# Spindle_Drive.net
KiCad netlist of a schematic drawn in Altium Designer
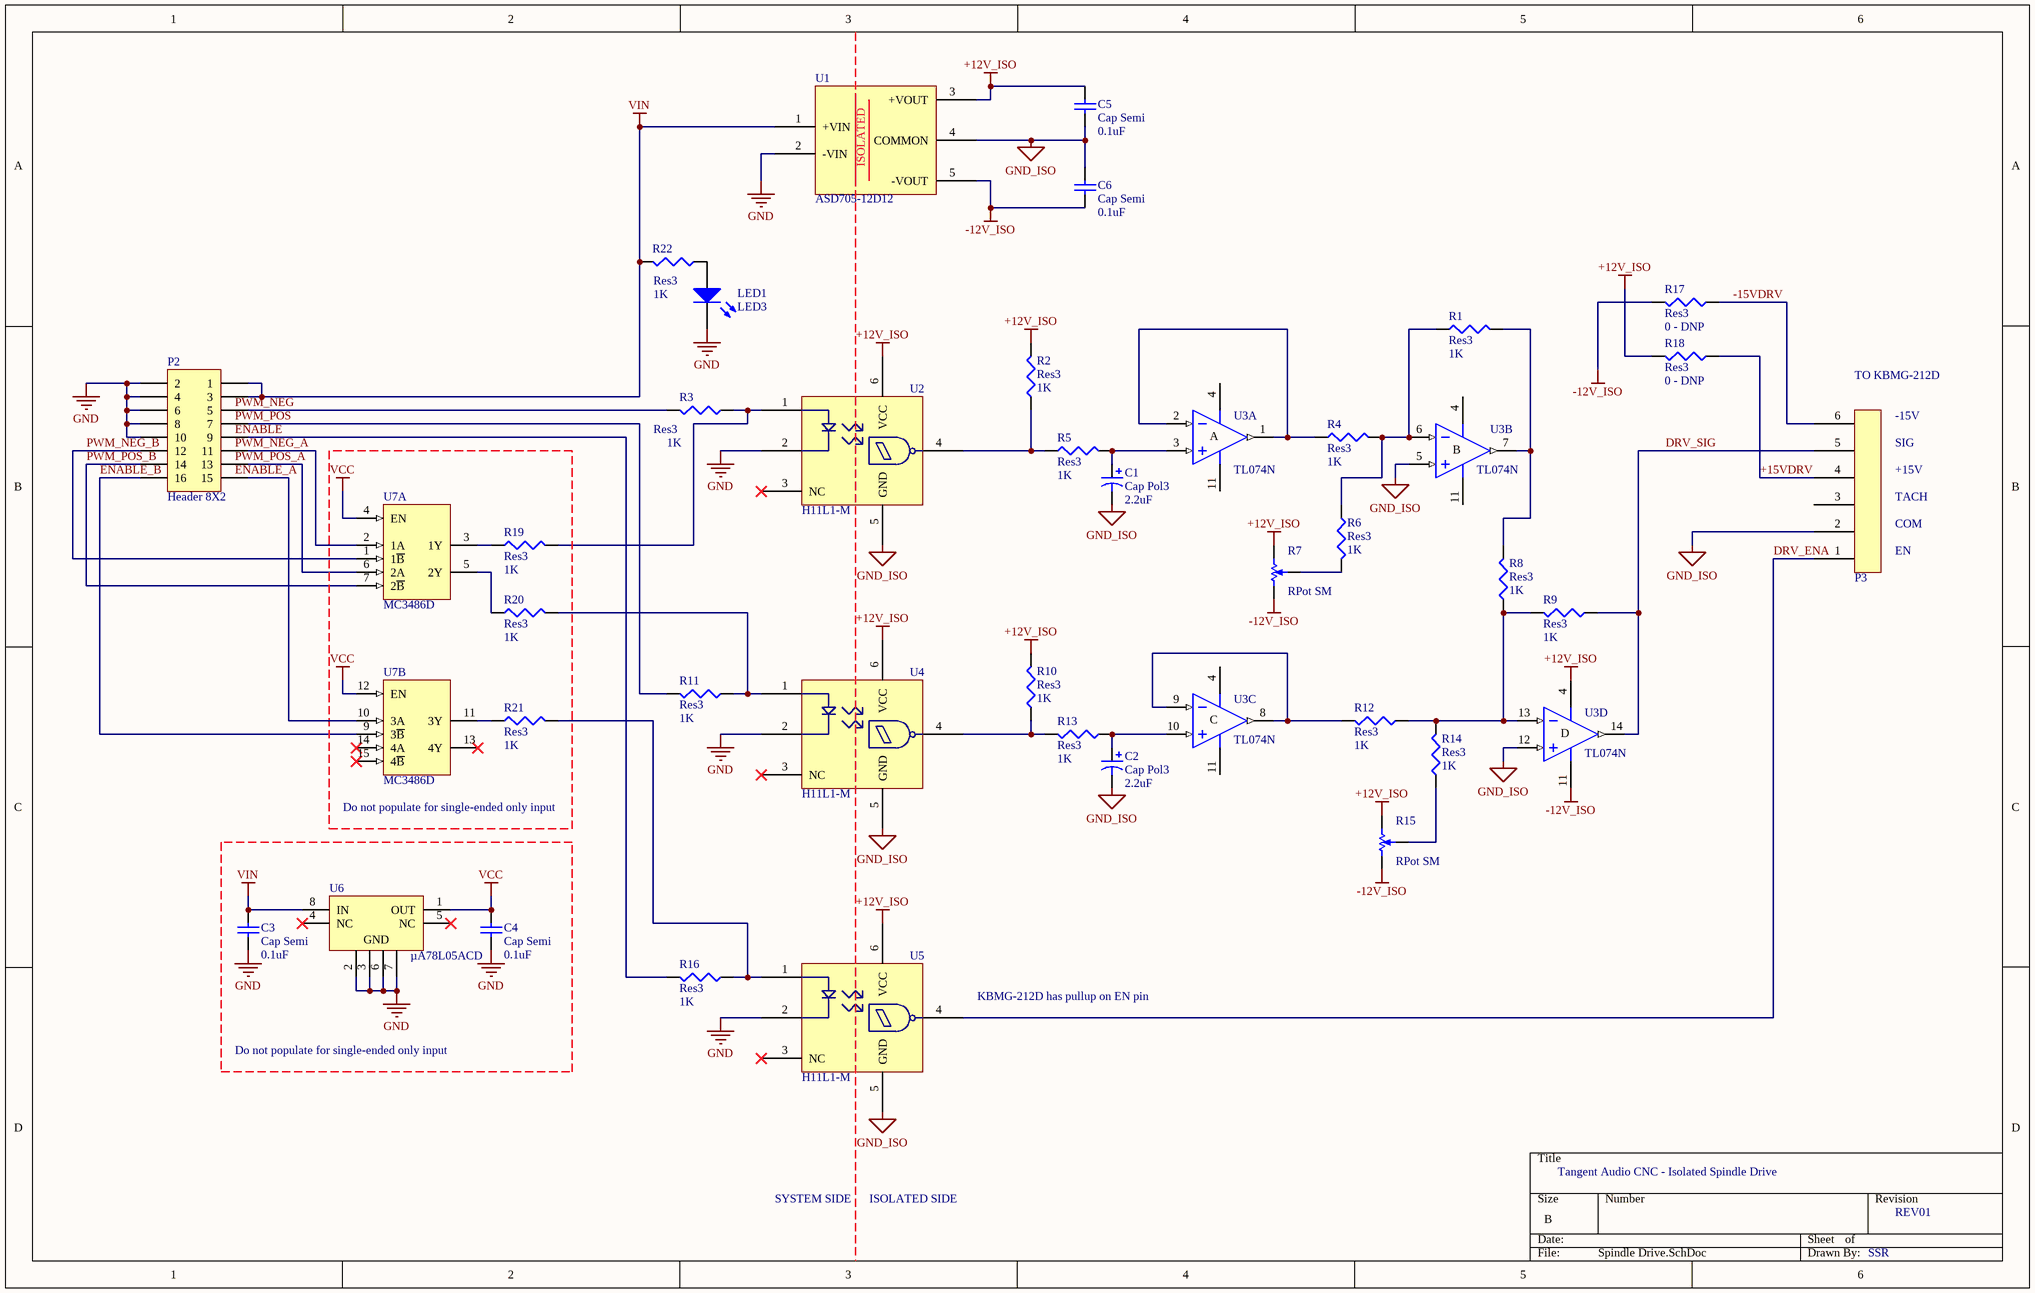
[diagram p0: Spindle Drive.SchDoc]

(export (version "E")
  (design (tool "Eeschema 10.0.6"))
  (components
    (comp (ref "C1")
      (value "Cap Pol3")
      (description "Polarized Capacitor (Surface Mount)")
      (fields (field (name "ALTIUM_VALUE") "2.2uF") (field (name "PUBLISHER") "Altium Limited"))
      (libsource (lib "Miscellaneous Devices") (part "Cap Pol3"))
    )
    (comp (ref "C2")
      (value "Cap Pol3")
      (description "Polarized Capacitor (Surface Mount)")
      (fields (field (name "ALTIUM_VALUE") "2.2uF") (field (name "PUBLISHER") "Altium Limited"))
      (libsource (lib "Miscellaneous Devices") (part "Cap Pol3"))
    )
    (comp (ref "C3")
      (value "Cap Semi")
      (footprint "1608[0603]")
      (description "Capacitor (Semiconductor SIM Model)")
      (fields (field (name "ALTIUM_VALUE") "0.1uF") (field (name "PUBLISHER") "Altium Limited"))
      (libsource (lib "Miscellaneous Devices") (part "Cap Semi"))
    )
    (comp (ref "C4")
      (value "Cap Semi")
      (footprint "1608[0603]")
      (description "Capacitor (Semiconductor SIM Model)")
      (fields (field (name "ALTIUM_VALUE") "0.1uF") (field (name "PUBLISHER") "Altium Limited"))
      (libsource (lib "Miscellaneous Devices") (part "Cap Semi"))
    )
    (comp (ref "C5")
      (value "Cap Semi")
      (footprint "1608[0603]")
      (description "Capacitor (Semiconductor SIM Model)")
      (fields (field (name "ALTIUM_VALUE") "0.1uF") (field (name "PUBLISHER") "Altium Limited"))
      (libsource (lib "Miscellaneous Devices") (part "Cap Semi"))
    )
    (comp (ref "C6")
      (value "Cap Semi")
      (footprint "1608[0603]")
      (description "Capacitor (Semiconductor SIM Model)")
      (fields (field (name "ALTIUM_VALUE") "0.1uF") (field (name "PUBLISHER") "Altium Limited"))
      (libsource (lib "Miscellaneous Devices") (part "Cap Semi"))
    )
    (comp (ref "LED1")
      (value "LED3")
      (footprint "3.5X2.8X1.9")
      (description "Typical BLUE SiC LED")
      (fields (field (name "PUBLISHER") "Altium Limited"))
      (libsource (lib "Miscellaneous Devices") (part "LED3"))
    )
    (comp (ref "P2")
      (value "Header 8X2")
      (footprint "IDC2.54-V16D")
      (description "Header, 8-Pin, Dual row")
      (fields (field (name "PUBLISHER") "Altium Limited"))
      (libsource (lib "Miscellaneous Connectors") (part "Header 8X2"))
    )
    (comp (ref "P3")
      (value "Phoenix_1933228")
      (footprint "Phoenix_1933228")
      (libsource (lib "GechoBreakout") (part "Phoenix_1933228"))
    )
    (comp (ref "R1")
      (value "Res3")
      (footprint "J1-0603")
      (description "Resistor")
      (fields (field (name "ALTIUM_VALUE") "1K") (field (name "PUBLISHER") "Altium Limited"))
      (libsource (lib "Miscellaneous Devices") (part "Res3"))
    )
    (comp (ref "R2")
      (value "Res3")
      (footprint "J1-0603")
      (description "Resistor")
      (fields (field (name "ALTIUM_VALUE") "1K") (field (name "PUBLISHER") "Altium Limited"))
      (libsource (lib "Miscellaneous Devices") (part "Res3"))
    )
    (comp (ref "R3")
      (value "Res3")
      (footprint "J1-0603")
      (description "Resistor")
      (fields (field (name "ALTIUM_VALUE") "1K") (field (name "PUBLISHER") "Altium Limited"))
      (libsource (lib "Miscellaneous Devices") (part "Res3"))
    )
    (comp (ref "R4")
      (value "Res3")
      (footprint "J1-0603")
      (description "Resistor")
      (fields (field (name "ALTIUM_VALUE") "1K") (field (name "PUBLISHER") "Altium Limited"))
      (libsource (lib "Miscellaneous Devices") (part "Res3"))
    )
    (comp (ref "R5")
      (value "Res3")
      (footprint "J1-0603")
      (description "Resistor")
      (fields (field (name "ALTIUM_VALUE") "1K") (field (name "PUBLISHER") "Altium Limited"))
      (libsource (lib "Miscellaneous Devices") (part "Res3"))
    )
    (comp (ref "R6")
      (value "Res3")
      (footprint "J1-0603")
      (description "Resistor")
      (fields (field (name "ALTIUM_VALUE") "1K") (field (name "PUBLISHER") "Altium Limited"))
      (libsource (lib "Miscellaneous Devices") (part "Res3"))
    )
    (comp (ref "R7")
      (value "RPot SM")
      (footprint "Copal_ST-4EA")
      (description "Square Trimming Potentiometer")
      (fields (field (name "PUBLISHER") "Altium Limited"))
      (libsource (lib "Miscellaneous Devices") (part "RPot SM"))
    )
    (comp (ref "R8")
      (value "Res3")
      (footprint "J1-0603")
      (description "Resistor")
      (fields (field (name "ALTIUM_VALUE") "1K") (field (name "PUBLISHER") "Altium Limited"))
      (libsource (lib "Miscellaneous Devices") (part "Res3"))
    )
    (comp (ref "R9")
      (value "Res3")
      (footprint "J1-0603")
      (description "Resistor")
      (fields (field (name "ALTIUM_VALUE") "1K") (field (name "PUBLISHER") "Altium Limited"))
      (libsource (lib "Miscellaneous Devices") (part "Res3"))
    )
    (comp (ref "R10")
      (value "Res3")
      (footprint "J1-0603")
      (description "Resistor")
      (fields (field (name "ALTIUM_VALUE") "1K") (field (name "PUBLISHER") "Altium Limited"))
      (libsource (lib "Miscellaneous Devices") (part "Res3"))
    )
    (comp (ref "R11")
      (value "Res3")
      (footprint "J1-0603")
      (description "Resistor")
      (fields (field (name "ALTIUM_VALUE") "1K") (field (name "PUBLISHER") "Altium Limited"))
      (libsource (lib "Miscellaneous Devices") (part "Res3"))
    )
    (comp (ref "R12")
      (value "Res3")
      (footprint "J1-0603")
      (description "Resistor")
      (fields (field (name "ALTIUM_VALUE") "1K") (field (name "PUBLISHER") "Altium Limited"))
      (libsource (lib "Miscellaneous Devices") (part "Res3"))
    )
    (comp (ref "R13")
      (value "Res3")
      (footprint "J1-0603")
      (description "Resistor")
      (fields (field (name "ALTIUM_VALUE") "1K") (field (name "PUBLISHER") "Altium Limited"))
      (libsource (lib "Miscellaneous Devices") (part "Res3"))
    )
    (comp (ref "R14")
      (value "Res3")
      (footprint "J1-0603")
      (description "Resistor")
      (fields (field (name "ALTIUM_VALUE") "1K") (field (name "PUBLISHER") "Altium Limited"))
      (libsource (lib "Miscellaneous Devices") (part "Res3"))
    )
    (comp (ref "R15")
      (value "RPot SM")
      (footprint "Copal_ST-4EA")
      (description "Square Trimming Potentiometer")
      (fields (field (name "PUBLISHER") "Altium Limited"))
      (libsource (lib "Miscellaneous Devices") (part "RPot SM"))
    )
    (comp (ref "R16")
      (value "Res3")
      (footprint "J1-0603")
      (description "Resistor")
      (fields (field (name "ALTIUM_VALUE") "1K") (field (name "PUBLISHER") "Altium Limited"))
      (libsource (lib "Miscellaneous Devices") (part "Res3"))
    )
    (comp (ref "R17")
      (value "Res3")
      (footprint "J1-0603")
      (description "Resistor")
      (fields (field (name "ALTIUM_VALUE") "0 - DNP") (field (name "PUBLISHER") "Altium Limited"))
      (libsource (lib "Miscellaneous Devices") (part "Res3"))
    )
    (comp (ref "R18")
      (value "Res3")
      (footprint "J1-0603")
      (description "Resistor")
      (fields (field (name "ALTIUM_VALUE") "0 - DNP") (field (name "PUBLISHER") "Altium Limited"))
      (libsource (lib "Miscellaneous Devices") (part "Res3"))
    )
    (comp (ref "R19")
      (value "Res3")
      (footprint "J1-0603")
      (description "Resistor")
      (fields (field (name "ALTIUM_VALUE") "1K") (field (name "PUBLISHER") "Altium Limited"))
      (libsource (lib "Miscellaneous Devices") (part "Res3"))
    )
    (comp (ref "R20")
      (value "Res3")
      (footprint "J1-0603")
      (description "Resistor")
      (fields (field (name "ALTIUM_VALUE") "1K") (field (name "PUBLISHER") "Altium Limited"))
      (libsource (lib "Miscellaneous Devices") (part "Res3"))
    )
    (comp (ref "R21")
      (value "Res3")
      (footprint "J1-0603")
      (description "Resistor")
      (fields (field (name "ALTIUM_VALUE") "1K") (field (name "PUBLISHER") "Altium Limited"))
      (libsource (lib "Miscellaneous Devices") (part "Res3"))
    )
    (comp (ref "R22")
      (value "Res3")
      (footprint "J1-0603")
      (description "Resistor")
      (fields (field (name "ALTIUM_VALUE") "1K") (field (name "PUBLISHER") "Altium Limited"))
      (libsource (lib "Miscellaneous Devices") (part "Res3"))
    )
    (comp (ref "U1")
      (value "ASD705-12D12")
      (footprint "Astrodyne_ASD705")
      (description "Astrodyne 9-18VDC in, +/-12VDC out iso regulated DC-DC")
      (libsource (lib "Spindle Drive") (part "ASD705-12D12"))
    )
    (comp (ref "U2")
      (value "H11L1-M")
      (footprint "H11L3M_SMT")
      (libsource (lib "Spindle Drive") (part "H11L1-M"))
    )
    (comp (ref "U3")
      (value "TL074N")
      (footprint "SOIC127P600-14AN")
      (description "Low-Noise JFET-Input Operational Amplifier")
      (fields (field (name "PUBLISHER") "Altium Limited"))
      (libsource (lib "TI Operational Amplifier") (part "TL074N"))
    )
    (comp (ref "U4")
      (value "H11L1-M")
      (footprint "H11L3M_SMT")
      (libsource (lib "Spindle Drive") (part "H11L1-M"))
    )
    (comp (ref "U5")
      (value "H11L1-M")
      (footprint "H11L3M_SMT")
      (libsource (lib "Spindle Drive") (part "H11L1-M"))
    )
    (comp (ref "U6")
      (value "µA78L05ACD")
      (footprint "D008_L")
      (description "Positive-Voltage Regulator")
      (fields (field (name "PUBLISHER") "Altium Limited"))
      (libsource (lib "TI Power Mgt Voltage Regulator") (part "µA78L05ACD"))
    )
    (comp (ref "U7")
      (value "MC3486D")
      (footprint "D016_N")
      (description "Quadruple Line Receiver with 3-State Output")
      (fields (field (name "PUBLISHER") "Altium Limited"))
      (libsource (lib "TI Interface Line Receiver") (part "MC3486D"))
    )
  )
  (nets
    (net (code "1") (name "+12V_ISO") (class "Default")
      (node (ref "C5") (pin "1") (pinfunction "1_1") (pintype "passive"))
      (node (ref "R10") (pin "2") (pinfunction "2_2") (pintype "passive"))
      (node (ref "R15") (pin "CW") (pinfunction "+_CW") (pintype "passive"))
      (node (ref "R18") (pin "2") (pinfunction "2_2") (pintype "passive"))
      (node (ref "R2") (pin "2") (pinfunction "2_2") (pintype "passive"))
      (node (ref "R7") (pin "CW") (pinfunction "+_CW") (pintype "passive"))
      (node (ref "U1") (pin "3") (pinfunction "+VOUT_3") (pintype "power_in"))
      (node (ref "U2") (pin "6") (pinfunction "VCC_6") (pintype "power_in"))
      (node (ref "U3") (pin "4") (pinfunction "V+_4") (pintype "power_in"))
      (node (ref "U4") (pin "6") (pinfunction "VCC_6") (pintype "power_in"))
      (node (ref "U5") (pin "6") (pinfunction "VCC_6") (pintype "power_in"))
    )
    (net (code "2") (name "-12V_ISO") (class "Default")
      (node (ref "C6") (pin "1") (pinfunction "1_1") (pintype "passive"))
      (node (ref "R15") (pin "CCW") (pinfunction "-_CCW") (pintype "passive"))
      (node (ref "R17") (pin "2") (pinfunction "2_2") (pintype "passive"))
      (node (ref "R7") (pin "CCW") (pinfunction "-_CCW") (pintype "passive"))
      (node (ref "U1") (pin "5") (pinfunction "-VOUT_5") (pintype "power_in"))
      (node (ref "U3") (pin "11") (pinfunction "V-_11") (pintype "power_in"))
    )
    (net (code "3") (name "/+15VDRV") (class "Default")
      (node (ref "P3") (pin "4") (pinfunction "4_4") (pintype "passive"))
      (node (ref "R18") (pin "1") (pinfunction "1_1") (pintype "passive"))
    )
    (net (code "4") (name "/-15VDRV") (class "Default")
      (node (ref "P3") (pin "6") (pinfunction "6_6") (pintype "passive"))
      (node (ref "R17") (pin "1") (pinfunction "1_1") (pintype "passive"))
    )
    (net (code "5") (name "/DRV_ENA") (class "Default")
      (node (ref "P3") (pin "1") (pinfunction "1_1") (pintype "passive"))
      (node (ref "U5") (pin "4") (pinfunction "VO_4") (pintype "passive"))
    )
    (net (code "6") (name "/DRV_SIG") (class "Default")
      (node (ref "P3") (pin "5") (pinfunction "5_5") (pintype "passive"))
      (node (ref "R9") (pin "1") (pinfunction "1_1") (pintype "passive"))
      (node (ref "U3") (pin "14") (pinfunction "OUT_14") (pintype "output"))
    )
    (net (code "9") (name "/ENABLE_B") (class "Default")
      (node (ref "P2") (pin "16") (pinfunction "16_16") (pintype "passive"))
      (node (ref "U7") (pin "9") (pinfunction "3~{B}_9") (pintype "input"))
    )
    (net (code "12") (name "/PWM_NEG_B") (class "Default")
      (node (ref "P2") (pin "12") (pinfunction "12_12") (pintype "passive"))
      (node (ref "U7") (pin "1") (pinfunction "1~{B}_1") (pintype "input"))
    )
    (net (code "15") (name "/PWM_POS_B") (class "Default")
      (node (ref "P2") (pin "14") (pinfunction "14_14") (pintype "passive"))
      (node (ref "U7") (pin "7") (pinfunction "2~{B}_7") (pintype "input"))
    )
    (net (code "16") (name "GND") (class "Default")
      (node (ref "C3") (pin "1") (pinfunction "1_1") (pintype "passive"))
      (node (ref "C4") (pin "1") (pinfunction "1_1") (pintype "passive"))
      (node (ref "LED1") (pin "2") (pinfunction "K_2") (pintype "passive"))
      (node (ref "P2") (pin "10") (pinfunction "10_10") (pintype "passive"))
      (node (ref "P2") (pin "2") (pinfunction "2_2") (pintype "passive"))
      (node (ref "P2") (pin "4") (pinfunction "4_4") (pintype "passive"))
      (node (ref "P2") (pin "6") (pinfunction "6_6") (pintype "passive"))
      (node (ref "P2") (pin "8") (pinfunction "8_8") (pintype "passive"))
      (node (ref "U1") (pin "2") (pinfunction "-VIN_2") (pintype "power_in"))
      (node (ref "U2") (pin "2") (pinfunction "K_2") (pintype "passive"))
      (node (ref "U4") (pin "2") (pinfunction "K_2") (pintype "passive"))
      (node (ref "U5") (pin "2") (pinfunction "K_2") (pintype "passive"))
      (node (ref "U6") (pin "2") (pinfunction "GND_2") (pintype "power_in"))
      (node (ref "U6") (pin "3") (pinfunction "GND_3") (pintype "power_in"))
      (node (ref "U6") (pin "6") (pinfunction "GND_6") (pintype "power_in"))
      (node (ref "U6") (pin "7") (pinfunction "GND_7") (pintype "power_in"))
      (node (ref "U7") (pin "8") (pinfunction "GND_8") (pintype "power_in"))
    )
    (net (code "17") (name "GND_ISO") (class "Default")
      (node (ref "C1") (pin "2") (pinfunction "2_2") (pintype "passive"))
      (node (ref "C2") (pin "2") (pinfunction "2_2") (pintype "passive"))
      (node (ref "C5") (pin "2") (pinfunction "2_2") (pintype "passive"))
      (node (ref "C6") (pin "2") (pinfunction "2_2") (pintype "passive"))
      (node (ref "P3") (pin "2") (pinfunction "2_2") (pintype "passive"))
      (node (ref "U1") (pin "4") (pinfunction "COMMON_4") (pintype "power_in"))
      (node (ref "U2") (pin "5") (pinfunction "GND_5") (pintype "power_in"))
      (node (ref "U3") (pin "12") (pinfunction "IN+_12") (pintype "input"))
      (node (ref "U3") (pin "5") (pinfunction "IN+_5") (pintype "input"))
      (node (ref "U4") (pin "5") (pinfunction "GND_5") (pintype "power_in"))
      (node (ref "U5") (pin "5") (pinfunction "GND_5") (pintype "power_in"))
    )
    (net (code "18") (name "Net-(LED1-A)") (class "Default")
      (node (ref "LED1") (pin "1") (pinfunction "A_1") (pintype "passive"))
      (node (ref "R22") (pin "1") (pinfunction "1_1") (pintype "passive"))
    )
    (net (code "19") (name "Net-(P2-Pad5)") (class "Default")
      (node (ref "P2") (pin "5") (pinfunction "5_5") (pintype "passive"))
      (node (ref "R3") (pin "2") (pinfunction "2_2") (pintype "passive"))
    )
    (net (code "20") (name "Net-(P2-Pad7)") (class "Default")
      (node (ref "P2") (pin "7") (pinfunction "7_7") (pintype "passive"))
      (node (ref "R11") (pin "2") (pinfunction "2_2") (pintype "passive"))
    )
    (net (code "21") (name "Net-(P2-Pad9)") (class "Default")
      (node (ref "P2") (pin "9") (pinfunction "9_9") (pintype "passive"))
      (node (ref "R16") (pin "2") (pinfunction "2_2") (pintype "passive"))
    )
    (net (code "22") (name "Net-(R6-Pad2)") (class "Default")
      (node (ref "R6") (pin "2") (pinfunction "2_2") (pintype "passive"))
      (node (ref "R7") (pin "W") (pinfunction "W_W") (pintype "passive"))
    )
    (net (code "23") (name "Net-(R14-Pad1)") (class "Default")
      (node (ref "R14") (pin "1") (pinfunction "1_1") (pintype "passive"))
      (node (ref "R15") (pin "W") (pinfunction "W_W") (pintype "passive"))
    )
    (net (code "24") (name "Net-(U2-A)") (class "Default")
      (node (ref "R19") (pin "2") (pinfunction "2_2") (pintype "passive"))
      (node (ref "R3") (pin "1") (pinfunction "1_1") (pintype "passive"))
      (node (ref "U2") (pin "1") (pinfunction "A_1") (pintype "passive"))
    )
    (net (code "25") (name "Net-(U2-VO)") (class "Default")
      (node (ref "R2") (pin "1") (pinfunction "1_1") (pintype "passive"))
      (node (ref "R5") (pin "1") (pinfunction "1_1") (pintype "passive"))
      (node (ref "U2") (pin "4") (pinfunction "VO_4") (pintype "passive"))
    )
    (net (code "26") (name "Net-(U3A-IN+)") (class "Default")
      (node (ref "C1") (pin "1") (pinfunction "1_1") (pintype "passive"))
      (node (ref "R5") (pin "2") (pinfunction "2_2") (pintype "passive"))
      (node (ref "U3") (pin "3") (pinfunction "IN+_3") (pintype "input"))
    )
    (net (code "27") (name "Net-(U3A-IN-)") (class "Default")
      (node (ref "R4") (pin "1") (pinfunction "1_1") (pintype "passive"))
      (node (ref "U3") (pin "1") (pinfunction "OUT_1") (pintype "output"))
      (node (ref "U3") (pin "2") (pinfunction "IN-_2") (pintype "input"))
    )
    (net (code "28") (name "Net-(U3B-IN-)") (class "Default")
      (node (ref "R1") (pin "1") (pinfunction "1_1") (pintype "passive"))
      (node (ref "R4") (pin "2") (pinfunction "2_2") (pintype "passive"))
      (node (ref "R6") (pin "1") (pinfunction "1_1") (pintype "passive"))
      (node (ref "U3") (pin "6") (pinfunction "IN-_6") (pintype "input"))
    )
    (net (code "29") (name "Net-(U3B-OUT)") (class "Default")
      (node (ref "R1") (pin "2") (pinfunction "2_2") (pintype "passive"))
      (node (ref "R8") (pin "2") (pinfunction "2_2") (pintype "passive"))
      (node (ref "U3") (pin "7") (pinfunction "OUT_7") (pintype "output"))
    )
    (net (code "30") (name "Net-(U3C-IN+)") (class "Default")
      (node (ref "C2") (pin "1") (pinfunction "1_1") (pintype "passive"))
      (node (ref "R13") (pin "1") (pinfunction "1_1") (pintype "passive"))
      (node (ref "U3") (pin "10") (pinfunction "IN+_10") (pintype "input"))
    )
    (net (code "31") (name "Net-(U3C-IN-)") (class "Default")
      (node (ref "R12") (pin "2") (pinfunction "2_2") (pintype "passive"))
      (node (ref "U3") (pin "8") (pinfunction "OUT_8") (pintype "output"))
      (node (ref "U3") (pin "9") (pinfunction "IN-_9") (pintype "input"))
    )
    (net (code "32") (name "Net-(U3D-IN-)") (class "Default")
      (node (ref "R12") (pin "1") (pinfunction "1_1") (pintype "passive"))
      (node (ref "R14") (pin "2") (pinfunction "2_2") (pintype "passive"))
      (node (ref "R8") (pin "1") (pinfunction "1_1") (pintype "passive"))
      (node (ref "R9") (pin "2") (pinfunction "2_2") (pintype "passive"))
      (node (ref "U3") (pin "13") (pinfunction "IN-_13") (pintype "input"))
    )
    (net (code "33") (name "Net-(U4-A)") (class "Default")
      (node (ref "R11") (pin "1") (pinfunction "1_1") (pintype "passive"))
      (node (ref "R20") (pin "2") (pinfunction "2_2") (pintype "passive"))
      (node (ref "U4") (pin "1") (pinfunction "A_1") (pintype "passive"))
    )
    (net (code "34") (name "Net-(U4-VO)") (class "Default")
      (node (ref "R10") (pin "1") (pinfunction "1_1") (pintype "passive"))
      (node (ref "R13") (pin "2") (pinfunction "2_2") (pintype "passive"))
      (node (ref "U4") (pin "4") (pinfunction "VO_4") (pintype "passive"))
    )
    (net (code "35") (name "Net-(U5-A)") (class "Default")
      (node (ref "R16") (pin "1") (pinfunction "1_1") (pintype "passive"))
      (node (ref "R21") (pin "2") (pinfunction "2_2") (pintype "passive"))
      (node (ref "U5") (pin "1") (pinfunction "A_1") (pintype "passive"))
    )
    (net (code "36") (name "Net-(U7A-1A)") (class "Default")
      (node (ref "P2") (pin "11") (pinfunction "11_11") (pintype "passive"))
      (node (ref "U7") (pin "2") (pinfunction "1A_2") (pintype "input"))
    )
    (net (code "37") (name "Net-(U7A-1Y)") (class "Default")
      (node (ref "R19") (pin "1") (pinfunction "1_1") (pintype "passive"))
      (node (ref "U7") (pin "3") (pinfunction "1Y_3") (pintype "tri_state"))
    )
    (net (code "38") (name "Net-(U7A-2A)") (class "Default")
      (node (ref "P2") (pin "13") (pinfunction "13_13") (pintype "passive"))
      (node (ref "U7") (pin "6") (pinfunction "2A_6") (pintype "input"))
    )
    (net (code "39") (name "Net-(U7A-2Y)") (class "Default")
      (node (ref "R20") (pin "1") (pinfunction "1_1") (pintype "passive"))
      (node (ref "U7") (pin "5") (pinfunction "2Y_5") (pintype "tri_state"))
    )
    (net (code "40") (name "Net-(U7B-3A)") (class "Default")
      (node (ref "P2") (pin "15") (pinfunction "15_15") (pintype "passive"))
      (node (ref "U7") (pin "10") (pinfunction "3A_10") (pintype "input"))
    )
    (net (code "41") (name "Net-(U7B-3Y)") (class "Default")
      (node (ref "R21") (pin "1") (pinfunction "1_1") (pintype "passive"))
      (node (ref "U7") (pin "11") (pinfunction "3Y_11") (pintype "tri_state"))
    )
    (net (code "42") (name "VCC") (class "Default")
      (node (ref "C4") (pin "2") (pinfunction "2_2") (pintype "passive"))
      (node (ref "U6") (pin "1") (pinfunction "OUT_1") (pintype "power_in"))
      (node (ref "U7") (pin "12") (pinfunction "EN_12") (pintype "input"))
      (node (ref "U7") (pin "16") (pinfunction "VCC_16") (pintype "power_in"))
      (node (ref "U7") (pin "4") (pinfunction "EN_4") (pintype "input"))
    )
    (net (code "43") (name "VIN") (class "Default")
      (node (ref "C3") (pin "2") (pinfunction "2_2") (pintype "passive"))
      (node (ref "P2") (pin "1") (pinfunction "1_1") (pintype "passive"))
      (node (ref "P2") (pin "3") (pinfunction "3_3") (pintype "passive"))
      (node (ref "R22") (pin "2") (pinfunction "2_2") (pintype "passive"))
      (node (ref "U1") (pin "1") (pinfunction "+VIN_1") (pintype "power_in"))
      (node (ref "U6") (pin "8") (pinfunction "IN_8") (pintype "power_in"))
    )
    (net (code "44") (name "unconnected-(P3-Pad3)") (class "Default")
      (node (ref "P3") (pin "3") (pinfunction "3_3") (pintype "passive"))
    )
    (net (code "45") (name "unconnected-(U2-NC-Pad3)") (class "Default")
      (node (ref "U2") (pin "3") (pinfunction "NC_3") (pintype "passive+no_connect"))
    )
    (net (code "46") (name "unconnected-(U3A-V+-Pad4)") (class "Default")
      (node (ref "U3") (pin "4") (pinfunction "V+_4") (pintype "power_in"))
    )
    (net (code "47") (name "unconnected-(U3A-V--Pad11)") (class "Default")
      (node (ref "U3") (pin "11") (pinfunction "V-_11") (pintype "power_in"))
    )
    (net (code "48") (name "unconnected-(U3B-V+-Pad4)") (class "Default")
      (node (ref "U3") (pin "4") (pinfunction "V+_4") (pintype "power_in"))
    )
    (net (code "49") (name "unconnected-(U3B-V--Pad11)") (class "Default")
      (node (ref "U3") (pin "11") (pinfunction "V-_11") (pintype "power_in"))
    )
    (net (code "50") (name "unconnected-(U3C-V+-Pad4)") (class "Default")
      (node (ref "U3") (pin "4") (pinfunction "V+_4") (pintype "power_in"))
    )
    (net (code "51") (name "unconnected-(U3C-V--Pad11)") (class "Default")
      (node (ref "U3") (pin "11") (pinfunction "V-_11") (pintype "power_in"))
    )
    (net (code "52") (name "unconnected-(U4-NC-Pad3)") (class "Default")
      (node (ref "U4") (pin "3") (pinfunction "NC_3") (pintype "passive+no_connect"))
    )
    (net (code "53") (name "unconnected-(U5-NC-Pad3)") (class "Default")
      (node (ref "U5") (pin "3") (pinfunction "NC_3") (pintype "passive+no_connect"))
    )
    (net (code "54") (name "unconnected-(U6-NC-Pad4)") (class "Default")
      (node (ref "U6") (pin "4") (pinfunction "NC_4") (pintype "passive+no_connect"))
    )
    (net (code "55") (name "unconnected-(U6-NC-Pad5)") (class "Default")
      (node (ref "U6") (pin "5") (pinfunction "NC_5") (pintype "passive+no_connect"))
    )
    (net (code "56") (name "unconnected-(U7B-4A-Pad14)") (class "Default")
      (node (ref "U7") (pin "14") (pinfunction "4A_14") (pintype "input+no_connect"))
    )
    (net (code "57") (name "unconnected-(U7B-4Y-Pad13)") (class "Default")
      (node (ref "U7") (pin "13") (pinfunction "4Y_13") (pintype "tri_state+no_connect"))
    )
    (net (code "58") (name "unconnected-(U7B-4~{B}-Pad15)") (class "Default")
      (node (ref "U7") (pin "15") (pinfunction "4~{B}_15") (pintype "input+no_connect"))
    )
  )
)
